# Variable_Output_2.net
KiCad netlist of a schematic drawn in Altium Designer
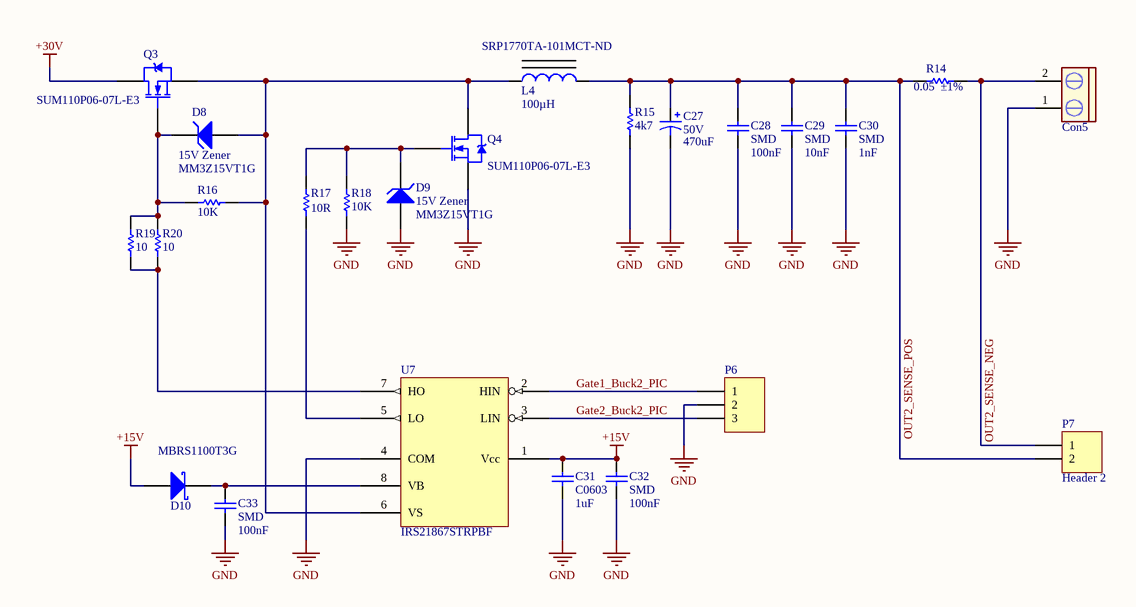
[diagram p0: Variable Output 2.SchDoc]

(export (version "E")
  (design (tool "Eeschema 10.0.6"))
  (components
    (comp (ref "C27")
      (value "50V")
      (footprint "CAPPR5-10X20")
      (description "Aluminum Electrolytic Capacitor, Radial Style with Long Leads: 470uF, 50V")
      (fields (field (name "ALTIUM_VALUE") "470uF") (field (name "PUBLISHER") "Altium Limited"))
      (libsource (lib "Vishay Roederstein Electrolytic Radial-Lead Capacitor") (part "EKB00DE347H00"))
    )
    (comp (ref "C28")
      (value "SMD")
      (footprint "1206")
      (description "Ceramic Chip Capacitor - Standard")
      (fields (field (name "ALTIUM_VALUE") "100nF") (field (name "PUBLISHER") "Altium Limited"))
      (libsource (lib "KEMET Chip Capacitor") (part "C1206"))
    )
    (comp (ref "C29")
      (value "SMD")
      (footprint "1206")
      (description "Ceramic Chip Capacitor - Standard")
      (fields (field (name "ALTIUM_VALUE") "10nF") (field (name "PUBLISHER") "Altium Limited"))
      (libsource (lib "KEMET Chip Capacitor") (part "C1206"))
    )
    (comp (ref "C30")
      (value "SMD")
      (footprint "1206")
      (description "Ceramic Chip Capacitor - Standard")
      (fields (field (name "ALTIUM_VALUE") "1nF") (field (name "PUBLISHER") "Altium Limited"))
      (libsource (lib "KEMET Chip Capacitor") (part "C1206"))
    )
    (comp (ref "C31")
      (value "C0603")
      (footprint "0603")
      (description "C1608X7R1C105K X7R")
      (fields (field (name "ALTIUM_VALUE") "1uF") (field (name "PUBLISHER") "Altium Limited"))
      (libsource (lib "KEMET Chip Capacitor") (part "C0603"))
    )
    (comp (ref "C32")
      (value "SMD")
      (footprint "1206")
      (description "Ceramic Chip Capacitor - Standard")
      (fields (field (name "ALTIUM_VALUE") "100nF") (field (name "PUBLISHER") "Altium Limited"))
      (libsource (lib "KEMET Chip Capacitor") (part "C1206"))
    )
    (comp (ref "C33")
      (value "SMD")
      (footprint "1206")
      (description "Ceramic Chip Capacitor - Standard")
      (fields (field (name "ALTIUM_VALUE") "100nF") (field (name "PUBLISHER") "Altium Limited"))
      (libsource (lib "KEMET Chip Capacitor") (part "C1206"))
    )
    (comp (ref "Con5")
      (value "Salida Buck")
      (footprint "My_CN2")
      (description "Connector blue screw")
      (libsource (lib "Mylib") (part "CON2 pin blue"))
    )
    (comp (ref "D8")
      (value "15V Zener")
      (footprint "SOD323")
      (description "Zener Diode")
      (fields
        (field (name "MANUFACTURER PART NUMBER") "MM3Z15VT1G")
        (field (name "TOLERANCE") "±5%")
        (field (name "MANUFACTURER") "ON Semiconductor")
      )
      (libsource (lib "Miscellaneous Devices") (part "D Zener"))
    )
    (comp (ref "D9")
      (value "15V Zener")
      (footprint "SOD323")
      (description "Zener Diode")
      (fields
        (field (name "MANUFACTURER PART NUMBER") "MM3Z15VT1G")
        (field (name "TOLERANCE") "±5%")
        (field (name "MANUFACTURER") "ON Semiconductor")
      )
      (libsource (lib "Miscellaneous Devices") (part "D Zener"))
    )
    (comp (ref "D10")
      (value "MBRS1100T3G")
      (footprint "SMB")
      (description "Generic Schottky Diode")
      (libsource (lib "NXT - Diodes") (part "Generic Schottky Diode"))
    )
    (comp (ref "L4")
      (value "Ferrite Inductor")
      (footprint "SRP1770TA Series")
      (fields
        (field (name "MANUFACTURER PART NUMBER") "SRP1770TA-101M")
        (field (name "TOLERANCE") "±20%")
        (field (name "SUPPLIER PART NUMBER") "SRP1770TA-101MCT-ND")
        (field (name "MANUFACTURER") "Bourns Inc.")
        (field (name "INDUCTANCE") "100µH")
      )
      (libsource (lib "NXT - Inductors") (part "Ferrite Inductor"))
    )
    (comp (ref "P6")
      (value "Header 3")
      (footprint "My_1X03")
      (description "Header, 3-Pin")
      (fields (field (name "PUBLISHER") "Altium Limited"))
      (libsource (lib "Mylib") (part "Header 3"))
    )
    (comp (ref "P7")
      (value "Header 2")
      (footprint "HDR1X2")
      (description "Header, 2-Pin")
      (fields (field (name "PUBLISHER") "Altium Limited"))
      (libsource (lib "Miscellaneous Connectors") (part "Header 2"))
    )
    (comp (ref "Q3")
      (value "SUM110P06")
      (footprint "D2PAK_N")
      (description "HEXFET Power MOSFET")
      (fields
        (field (name "MANUFACTURER PART NUMBER") "SUM110P06-07L-E3")
        (field (name "MANUFACTURER") "Vishay Siliconix")
      )
      (libsource (lib "IR Discrete MOSFET - Power") (part "IRF540NS"))
    )
    (comp (ref "Q4")
      (value "SUM110P06")
      (footprint "D2PAK_N")
      (description "HEXFET Power MOSFET")
      (fields
        (field (name "MANUFACTURER PART NUMBER") "SUM110P06-07L-E3")
        (field (name "MANUFACTURER") "Vishay Siliconix")
      )
      (libsource (lib "IR Discrete MOSFET - Power") (part "IRF540NS"))
    )
    (comp (ref "R14")
      (value "ERJL1W")
      (footprint "L1W-2512")
      (fields
        (field (name "MANUFACTURER PART NUMBER") "PE2512FKE070R05L")
        (field (name "MANUFACTURER") "Yageo")
        (field (name "RESISTANCE (OHMS)") "0.05")
        (field (name "TOLERANCE") "±1%")
        (field (name "PUBLISHER") "Altium Limited")
      )
      (libsource (lib "Panasonic Resistor") (part "ERJL1W"))
    )
    (comp (ref "R15")
      (value "4k7")
      (footprint "8RB-1206")
      (fields (field (name "Comment") "SMD") (field (name "PUBLISHER") "Altium Limited"))
      (libsource (lib "Panasonic Resistor") (part "ERJ8BQ"))
    )
    (comp (ref "R16")
      (value "10K")
      (footprint "ERA-0603")
      (fields (field (name "PUBLISHER") "Altium Limited"))
      (libsource (lib "Panasonic Resistor") (part "ERA3Y"))
    )
    (comp (ref "R17")
      (value "10R")
      (footprint "8RB-1206")
      (fields (field (name "Comment") "SMD 1206") (field (name "PUBLISHER") "Altium Limited"))
      (libsource (lib "Panasonic Resistor") (part "ERJ8BQ"))
    )
    (comp (ref "R18")
      (value "10K")
      (footprint "ERA-0603")
      (fields (field (name "PUBLISHER") "Altium Limited"))
      (libsource (lib "Panasonic Resistor") (part "ERA3Y"))
    )
    (comp (ref "R19")
      (value "10")
      (footprint "ERA-0603")
      (fields (field (name "PUBLISHER") "Altium Limited"))
      (libsource (lib "Panasonic Resistor") (part "ERA3Y"))
    )
    (comp (ref "R20")
      (value "10")
      (footprint "ERA-0603")
      (fields (field (name "PUBLISHER") "Altium Limited"))
      (libsource (lib "Panasonic Resistor") (part "ERA3Y"))
    )
    (comp (ref "U7")
      (value "IRS21867S")
      (footprint "SOIC8")
      (description "Half-Bridge Gate Driver IC Inverting 8-SOIC")
      (fields
        (field (name "MANUFACTURER") "Infineon Technologies")
        (field (name "MANUFACTURER PART NUMBER") "IRS21867STRPBF")
      )
      (libsource (lib "NXT - IC") (part "IRS21867S"))
    )
  )
  (nets
    (net (code "1") (name "+15V") (class "Default")
      (node (ref "C31") (pin "2") (pinfunction "2_2") (pintype "passive"))
      (node (ref "C32") (pin "2") (pinfunction "2_2") (pintype "passive"))
      (node (ref "D10") (pin "1") (pinfunction "A_1") (pintype "passive"))
      (node (ref "U7") (pin "1") (pinfunction "Vcc_1") (pintype "power_in"))
    )
    (net (code "2") (name "+30V") (class "Default")
      (node (ref "Q3") (pin "2") (pinfunction "D_2") (pintype "passive"))
    )
    (net (code "3") (name "/Gate1_Buck2_PIC") (class "Default")
      (node (ref "P6") (pin "1") (pinfunction "1_1") (pintype "passive"))
      (node (ref "U7") (pin "2") (pinfunction "HIN_2") (pintype "input"))
    )
    (net (code "4") (name "/Gate2_Buck2_PIC") (class "Default")
      (node (ref "P6") (pin "3") (pinfunction "3_3") (pintype "passive"))
      (node (ref "U7") (pin "3") (pinfunction "LIN_3") (pintype "input"))
    )
    (net (code "5") (name "/OUT2_SENSE_NEG") (class "Default")
      (node (ref "Con5") (pin "2") (pinfunction "2_2") (pintype "passive"))
      (node (ref "P7") (pin "1") (pinfunction "1_1") (pintype "passive"))
      (node (ref "R14") (pin "2") (pinfunction "2_2") (pintype "passive"))
    )
    (net (code "6") (name "/OUT2_SENSE_POS") (class "Default")
      (node (ref "C27") (pin "1") (pinfunction "1_1") (pintype "passive"))
      (node (ref "C28") (pin "2") (pinfunction "2_2") (pintype "passive"))
      (node (ref "C29") (pin "2") (pinfunction "2_2") (pintype "passive"))
      (node (ref "C30") (pin "2") (pinfunction "2_2") (pintype "passive"))
      (node (ref "L4") (pin "2") (pinfunction "2_2") (pintype "passive"))
      (node (ref "P7") (pin "2") (pinfunction "2_2") (pintype "passive"))
      (node (ref "R14") (pin "1") (pinfunction "1_1") (pintype "passive"))
      (node (ref "R15") (pin "2") (pinfunction "2_2") (pintype "passive"))
    )
    (net (code "7") (name "GND") (class "Default")
      (node (ref "C27") (pin "2") (pinfunction "2_2") (pintype "passive"))
      (node (ref "C28") (pin "1") (pinfunction "1_1") (pintype "passive"))
      (node (ref "C29") (pin "1") (pinfunction "1_1") (pintype "passive"))
      (node (ref "C30") (pin "1") (pinfunction "1_1") (pintype "passive"))
      (node (ref "C31") (pin "1") (pinfunction "1_1") (pintype "passive"))
      (node (ref "C32") (pin "1") (pinfunction "1_1") (pintype "passive"))
      (node (ref "C33") (pin "1") (pinfunction "1_1") (pintype "passive"))
      (node (ref "Con5") (pin "1") (pinfunction "1_1") (pintype "passive"))
      (node (ref "D9") (pin "1") (pinfunction "A_1") (pintype "passive"))
      (node (ref "P6") (pin "2") (pinfunction "2_2") (pintype "passive"))
      (node (ref "Q4") (pin "3") (pinfunction "S_3") (pintype "passive"))
      (node (ref "R15") (pin "1") (pinfunction "1_1") (pintype "passive"))
      (node (ref "R18") (pin "1") (pinfunction "1_1") (pintype "passive"))
      (node (ref "U7") (pin "4") (pinfunction "COM_4") (pintype "passive"))
    )
    (net (code "8") (name "Net-(D8-A)") (class "Default")
      (node (ref "D8") (pin "1") (pinfunction "A_1") (pintype "passive"))
      (node (ref "L4") (pin "1") (pinfunction "1_1") (pintype "passive"))
      (node (ref "Q3") (pin "3") (pinfunction "S_3") (pintype "passive"))
      (node (ref "Q4") (pin "2") (pinfunction "D_2") (pintype "passive"))
      (node (ref "R16") (pin "2") (pinfunction "2_2") (pintype "passive"))
      (node (ref "U7") (pin "6") (pinfunction "VS_6") (pintype "passive"))
    )
    (net (code "9") (name "Net-(D8-K)") (class "Default")
      (node (ref "D8") (pin "2") (pinfunction "K_2") (pintype "passive"))
      (node (ref "Q3") (pin "1") (pinfunction "G_1") (pintype "passive"))
      (node (ref "R16") (pin "1") (pinfunction "1_1") (pintype "passive"))
      (node (ref "R19") (pin "2") (pinfunction "2_2") (pintype "passive"))
      (node (ref "R20") (pin "2") (pinfunction "2_2") (pintype "passive"))
    )
    (net (code "10") (name "Net-(D9-K)") (class "Default")
      (node (ref "D9") (pin "2") (pinfunction "K_2") (pintype "passive"))
      (node (ref "Q4") (pin "1") (pinfunction "G_1") (pintype "passive"))
      (node (ref "R17") (pin "1") (pinfunction "1_1") (pintype "passive"))
      (node (ref "R18") (pin "2") (pinfunction "2_2") (pintype "passive"))
    )
    (net (code "11") (name "Net-(D10-K)") (class "Default")
      (node (ref "C33") (pin "2") (pinfunction "2_2") (pintype "passive"))
      (node (ref "D10") (pin "2") (pinfunction "K_2") (pintype "passive"))
      (node (ref "U7") (pin "8") (pinfunction "VB_8") (pintype "passive"))
    )
    (net (code "12") (name "Net-(U7-HO)") (class "Default")
      (node (ref "R19") (pin "1") (pinfunction "1_1") (pintype "passive"))
      (node (ref "R20") (pin "1") (pinfunction "1_1") (pintype "passive"))
      (node (ref "U7") (pin "7") (pinfunction "HO_7") (pintype "output"))
    )
    (net (code "13") (name "Net-(U7-LO)") (class "Default")
      (node (ref "R17") (pin "2") (pinfunction "2_2") (pintype "passive"))
      (node (ref "U7") (pin "5") (pinfunction "LO_5") (pintype "output"))
    )
  )
)
